# STM32.net
KiCad netlist of a schematic drawn in Altium Designer
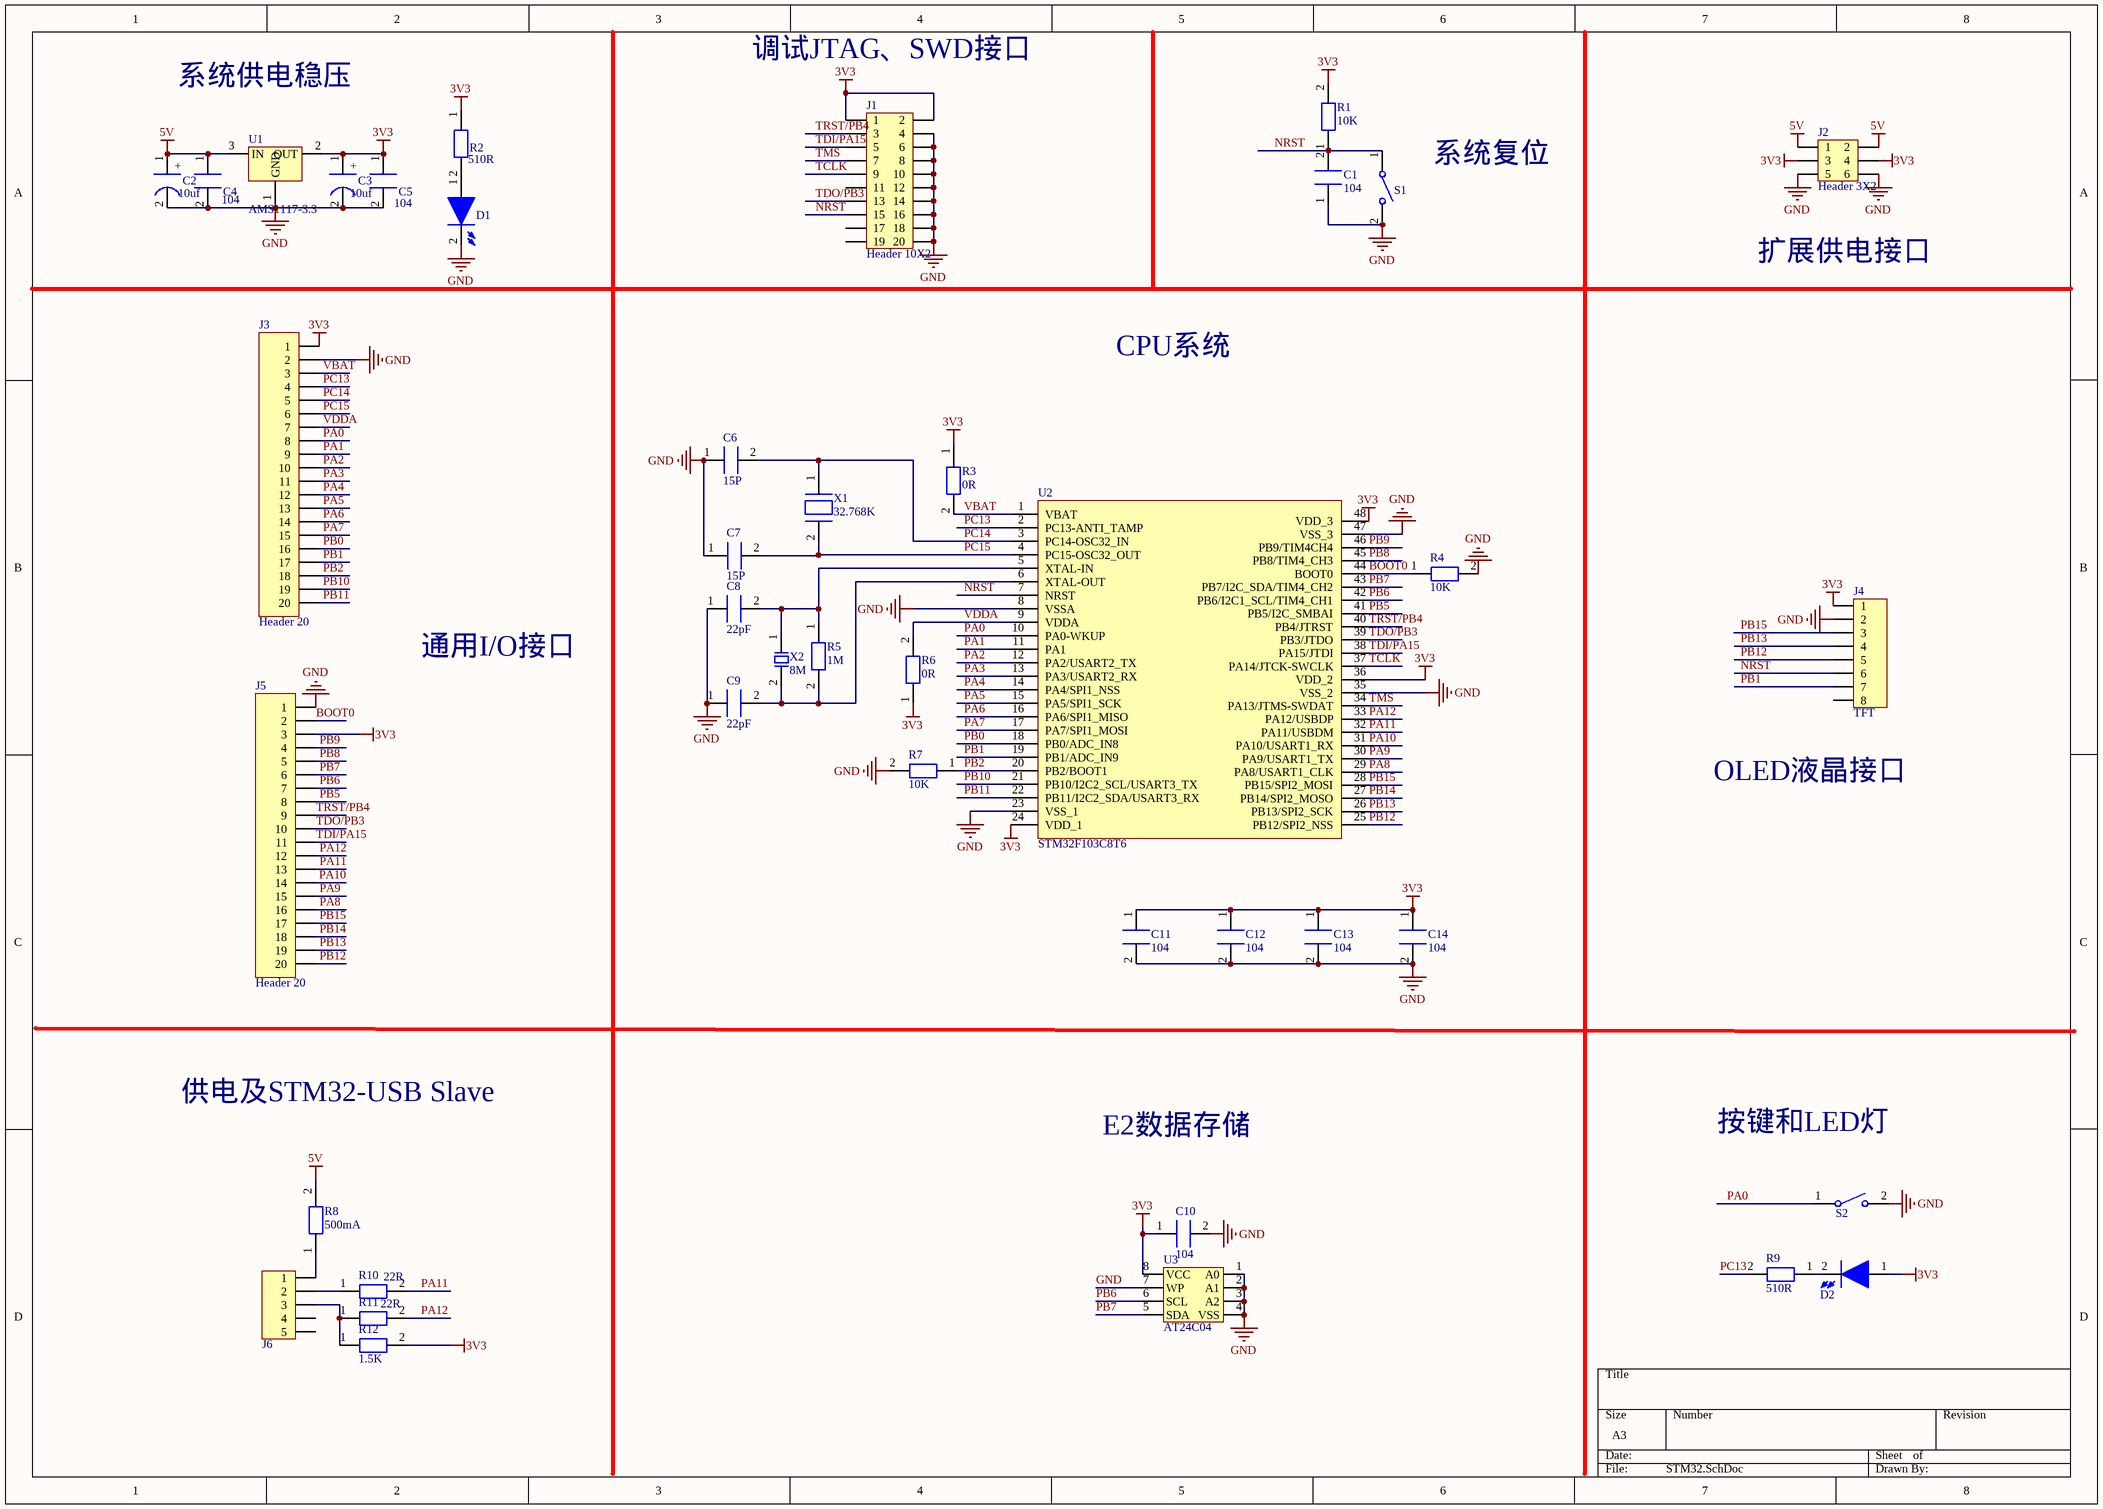
[diagram p0: STM32.SchDoc]

(export (version "E")
  (design (tool "Eeschema 10.0.6"))
  (components
    (comp (ref "C1")
      (value "104")
      (footprint "RC0603")
      (description "电容")
      (libsource (lib "STM32") (part "CAP"))
    )
    (comp (ref "C2")
      (value "10uf")
      (footprint "0805")
      (description "极性电容")
      (libsource (lib "STM32") (part "CAP+"))
    )
    (comp (ref "C3")
      (value "10uf")
      (footprint "0805")
      (description "极性电容")
      (libsource (lib "STM32") (part "CAP+"))
    )
    (comp (ref "C4")
      (value "104")
      (footprint "RC0603")
      (description "电容")
      (libsource (lib "STM32") (part "CAP"))
    )
    (comp (ref "C5")
      (value "104")
      (footprint "RC0603")
      (description "电容")
      (libsource (lib "STM32") (part "CAP"))
    )
    (comp (ref "C6")
      (value "15P")
      (footprint "RC0603")
      (description "电容")
      (libsource (lib "STM32") (part "CAP"))
    )
    (comp (ref "C7")
      (value "15P")
      (footprint "RC0603")
      (description "电容")
      (libsource (lib "STM32") (part "CAP"))
    )
    (comp (ref "C8")
      (value "22pF")
      (footprint "RC0603")
      (description "电容")
      (libsource (lib "STM32") (part "CAP"))
    )
    (comp (ref "C9")
      (value "22pF")
      (footprint "RC0603")
      (description "电容")
      (libsource (lib "STM32") (part "CAP"))
    )
    (comp (ref "C10")
      (value "104")
      (footprint "RC0603")
      (description "电容")
      (libsource (lib "STM32") (part "CAP"))
    )
    (comp (ref "C11")
      (value "104")
      (footprint "RC0603")
      (description "电容")
      (libsource (lib "STM32") (part "CAP"))
    )
    (comp (ref "C12")
      (value "104")
      (footprint "RC0603")
      (description "电容")
      (libsource (lib "STM32") (part "CAP"))
    )
    (comp (ref "C13")
      (value "104")
      (footprint "RC0603")
      (description "电容")
      (libsource (lib "STM32") (part "CAP"))
    )
    (comp (ref "C14")
      (value "104")
      (footprint "RC0603")
      (description "电容")
      (libsource (lib "STM32") (part "CAP"))
    )
    (comp (ref "D1")
      (value "LED0")
      (footprint "LED0805")
      (description "LED")
      (libsource (lib "STM32") (part "LED0"))
    )
    (comp (ref "D2")
      (value "LED0")
      (footprint "LED0805")
      (description "LED")
      (libsource (lib "STM32") (part "LED0"))
    )
    (comp (ref "J1")
      (value "Header 10X2")
      (footprint "JTAG_20P")
      (libsource (lib "STM32") (part "Header 10X2"))
    )
    (comp (ref "J2") (value "Header 3X2") (footprint "H-3X2") (libsource (lib "STM32") (part "Header 3X2")))
    (comp (ref "J3") (value "Header 20") (footprint "H 20") (libsource (lib "STM32") (part "Header 20")))
    (comp (ref "J4") (value "TFT") (footprint "H-8") (libsource (lib "STM32") (part "TFT")))
    (comp (ref "J5") (value "Header 20") (footprint "H 20") (libsource (lib "STM32") (part "Header 20")))
    (comp (ref "J6") (value "Mini-USB") (footprint "mini_USB") (libsource (lib "STM32") (part "Mini-USB")))
    (comp (ref "R1")
      (value "10K")
      (footprint "RC0603")
      (description "电阻")
      (libsource (lib "STM32") (part "RES"))
    )
    (comp (ref "R2")
      (value "510R")
      (footprint "RC0603")
      (description "电阻")
      (libsource (lib "STM32") (part "RES"))
    )
    (comp (ref "R3")
      (value "0R")
      (footprint "RC0603")
      (description "电阻")
      (libsource (lib "STM32") (part "RES"))
    )
    (comp (ref "R4")
      (value "10K")
      (footprint "RC0603")
      (description "电阻")
      (libsource (lib "STM32") (part "RES"))
    )
    (comp (ref "R5")
      (value "1M")
      (footprint "RC0603")
      (description "电阻")
      (libsource (lib "STM32") (part "RES"))
    )
    (comp (ref "R6")
      (value "0R")
      (footprint "RC0603")
      (description "电阻")
      (libsource (lib "STM32") (part "RES"))
    )
    (comp (ref "R7")
      (value "10K")
      (footprint "RC0603")
      (description "电阻")
      (libsource (lib "STM32") (part "RES"))
    )
    (comp (ref "R8")
      (value "500mA")
      (footprint "0805")
      (description "电阻")
      (libsource (lib "STM32") (part "RES"))
    )
    (comp (ref "R9")
      (value "510R")
      (footprint "RC0603")
      (description "电阻")
      (libsource (lib "STM32") (part "RES"))
    )
    (comp (ref "R10")
      (value "22R")
      (footprint "RC0603")
      (description "电阻")
      (libsource (lib "STM32") (part "RES"))
    )
    (comp (ref "R11")
      (value "22R")
      (footprint "RC0603")
      (description "电阻")
      (libsource (lib "STM32") (part "RES"))
    )
    (comp (ref "R12")
      (value "1.5K")
      (footprint "RC0603")
      (description "电阻")
      (libsource (lib "STM32") (part "RES"))
    )
    (comp (ref "S1")
      (value "SW-SPST")
      (footprint "SMT-KEY")
      (description "开关")
      (libsource (lib "STM32") (part "SW-SPST"))
    )
    (comp (ref "S2")
      (value "SW-SPST")
      (footprint "SMT-KEY")
      (description "开关")
      (libsource (lib "STM32") (part "SW-SPST"))
    )
    (comp (ref "U1")
      (value "AMS1117-3.3")
      (footprint "SOT223")
      (description "IC")
      (libsource (lib "STM32") (part "AMS1117-3.3"))
    )
    (comp (ref "U2")
      (value "STM32F103C8T6")
      (footprint "LQFP48")
      (description "IC")
      (libsource (lib "STM32") (part "STM32F103C8T6"))
    )
    (comp (ref "U3")
      (value "AT24C04")
      (footprint "SOIC-8")
      (description "IC")
      (libsource (lib "STM32") (part "AT24C04"))
    )
    (comp (ref "X1") (value "32.768K") (footprint "JZ32768") (libsource (lib "STM32") (part "32.768K")))
    (comp (ref "X2") (value "8M") (footprint "JZ49S") (libsource (lib "STM32") (part "8M")))
  )
  (nets
    (net (code "1") (name "/BOOT0") (class "Default")
      (node (ref "J5") (pin "2") (pinfunction "2_2") (pintype "passive"))
      (node (ref "R4") (pin "1") (pinfunction "1_1") (pintype "passive"))
      (node (ref "U2") (pin "44") (pinfunction "BOOT0_44") (pintype "passive"))
    )
    (net (code "2") (name "/NRST") (class "Default")
      (node (ref "C1") (pin "2") (pinfunction "2_2") (pintype "passive"))
      (node (ref "J1") (pin "15") (pinfunction "15_15") (pintype "passive"))
      (node (ref "J4") (pin "6") (pinfunction "6_6") (pintype "passive"))
      (node (ref "R1") (pin "1") (pinfunction "1_1") (pintype "passive"))
      (node (ref "S1") (pin "1") (pinfunction "1_1") (pintype "passive"))
      (node (ref "U2") (pin "7") (pinfunction "NRST_7") (pintype "passive"))
    )
    (net (code "3") (name "/PA0") (class "Default")
      (node (ref "J3") (pin "8") (pinfunction "8_8") (pintype "passive"))
      (node (ref "S2") (pin "1") (pinfunction "1_1") (pintype "passive"))
      (node (ref "U2") (pin "10") (pinfunction "PA0-WKUP_10") (pintype "passive"))
    )
    (net (code "4") (name "/PA1") (class "Default")
      (node (ref "J3") (pin "9") (pinfunction "9_9") (pintype "passive"))
      (node (ref "U2") (pin "11") (pinfunction "PA1_11") (pintype "passive"))
    )
    (net (code "5") (name "/PA2") (class "Default")
      (node (ref "J3") (pin "10") (pinfunction "10_10") (pintype "passive"))
      (node (ref "U2") (pin "12") (pinfunction "PA2/USART2_TX_12") (pintype "passive"))
    )
    (net (code "6") (name "/PA3") (class "Default")
      (node (ref "J3") (pin "11") (pinfunction "11_11") (pintype "passive"))
      (node (ref "U2") (pin "13") (pinfunction "PA3/USART2_RX_13") (pintype "passive"))
    )
    (net (code "7") (name "/PA4") (class "Default")
      (node (ref "J3") (pin "12") (pinfunction "12_12") (pintype "passive"))
      (node (ref "U2") (pin "14") (pinfunction "PA4/SPI1_NSS_14") (pintype "passive"))
    )
    (net (code "8") (name "/PA5") (class "Default")
      (node (ref "J3") (pin "13") (pinfunction "13_13") (pintype "passive"))
      (node (ref "U2") (pin "15") (pinfunction "PA5/SPI1_SCK_15") (pintype "passive"))
    )
    (net (code "9") (name "/PA6") (class "Default")
      (node (ref "J3") (pin "14") (pinfunction "14_14") (pintype "passive"))
      (node (ref "U2") (pin "16") (pinfunction "PA6/SPI1_MISO_16") (pintype "passive"))
    )
    (net (code "10") (name "/PA7") (class "Default")
      (node (ref "J3") (pin "15") (pinfunction "15_15") (pintype "passive"))
      (node (ref "U2") (pin "17") (pinfunction "PA7/SPI1_MOSI_17") (pintype "passive"))
    )
    (net (code "11") (name "/PA8") (class "Default")
      (node (ref "J5") (pin "16") (pinfunction "16_16") (pintype "passive"))
      (node (ref "U2") (pin "29") (pinfunction "PA8/USART1_CLK_29") (pintype "passive"))
    )
    (net (code "12") (name "/PA9") (class "Default")
      (node (ref "J5") (pin "15") (pinfunction "15_15") (pintype "passive"))
      (node (ref "U2") (pin "30") (pinfunction "PA9/USART1_TX_30") (pintype "passive"))
    )
    (net (code "13") (name "/PA10") (class "Default")
      (node (ref "J5") (pin "14") (pinfunction "14_14") (pintype "passive"))
      (node (ref "U2") (pin "31") (pinfunction "PA10/USART1_RX_31") (pintype "passive"))
    )
    (net (code "14") (name "/PA11") (class "Default")
      (node (ref "J5") (pin "13") (pinfunction "13_13") (pintype "passive"))
      (node (ref "R10") (pin "2") (pinfunction "2_2") (pintype "passive"))
      (node (ref "U2") (pin "32") (pinfunction "PA11/USBDM_32") (pintype "passive"))
    )
    (net (code "15") (name "/PA12") (class "Default")
      (node (ref "J5") (pin "12") (pinfunction "12_12") (pintype "passive"))
      (node (ref "R11") (pin "2") (pinfunction "2_2") (pintype "passive"))
      (node (ref "U2") (pin "33") (pinfunction "PA12/USBDP_33") (pintype "passive"))
    )
    (net (code "16") (name "/PB0") (class "Default")
      (node (ref "J3") (pin "16") (pinfunction "16_16") (pintype "passive"))
      (node (ref "U2") (pin "18") (pinfunction "PB0/ADC_IN8_18") (pintype "passive"))
    )
    (net (code "17") (name "/PB1") (class "Default")
      (node (ref "J3") (pin "17") (pinfunction "17_17") (pintype "passive"))
      (node (ref "J4") (pin "7") (pinfunction "7_7") (pintype "passive"))
      (node (ref "U2") (pin "19") (pinfunction "PB1/ADC_IN9_19") (pintype "passive"))
    )
    (net (code "18") (name "/PB2") (class "Default")
      (node (ref "J3") (pin "18") (pinfunction "18_18") (pintype "passive"))
      (node (ref "R7") (pin "1") (pinfunction "1_1") (pintype "passive"))
      (node (ref "U2") (pin "20") (pinfunction "PB2/BOOT1_20") (pintype "passive"))
    )
    (net (code "19") (name "/PB5") (class "Default")
      (node (ref "J5") (pin "8") (pinfunction "8_8") (pintype "passive"))
      (node (ref "U2") (pin "41") (pinfunction "PB5/I2C_SMBAI_41") (pintype "passive"))
    )
    (net (code "20") (name "/PB6") (class "Default")
      (node (ref "J5") (pin "7") (pinfunction "7_7") (pintype "passive"))
      (node (ref "U2") (pin "42") (pinfunction "PB6/I2C1_SCL/TIM4_CH1_42") (pintype "passive"))
      (node (ref "U3") (pin "6") (pinfunction "SCL_6") (pintype "passive"))
    )
    (net (code "21") (name "/PB7") (class "Default")
      (node (ref "J5") (pin "6") (pinfunction "6_6") (pintype "passive"))
      (node (ref "U2") (pin "43") (pinfunction "PB7/I2C_SDA/TIM4_CH2_43") (pintype "passive"))
      (node (ref "U3") (pin "5") (pinfunction "SDA_5") (pintype "passive"))
    )
    (net (code "22") (name "/PB8") (class "Default")
      (node (ref "J5") (pin "5") (pinfunction "5_5") (pintype "passive"))
      (node (ref "U2") (pin "45") (pinfunction "PB8/TIM4_CH3_45") (pintype "passive"))
    )
    (net (code "23") (name "/PB9") (class "Default")
      (node (ref "J5") (pin "4") (pinfunction "4_4") (pintype "passive"))
      (node (ref "U2") (pin "46") (pinfunction "PB9/TIM4CH4_46") (pintype "passive"))
    )
    (net (code "24") (name "/PB10") (class "Default")
      (node (ref "J3") (pin "19") (pinfunction "19_19") (pintype "passive"))
      (node (ref "U2") (pin "21") (pinfunction "PB10/I2C2_SCL/USART3_TX_21") (pintype "passive"))
    )
    (net (code "25") (name "/PB11") (class "Default")
      (node (ref "J3") (pin "20") (pinfunction "20_20") (pintype "passive"))
      (node (ref "U2") (pin "22") (pinfunction "PB11/I2C2_SDA/USART3_RX_22") (pintype "passive"))
    )
    (net (code "26") (name "/PB12") (class "Default")
      (node (ref "J4") (pin "5") (pinfunction "5_5") (pintype "passive"))
      (node (ref "J5") (pin "20") (pinfunction "20_20") (pintype "passive"))
      (node (ref "U2") (pin "25") (pinfunction "PB12/SPI2_NSS_25") (pintype "passive"))
    )
    (net (code "27") (name "/PB13") (class "Default")
      (node (ref "J4") (pin "4") (pinfunction "4_4") (pintype "passive"))
      (node (ref "J5") (pin "19") (pinfunction "19_19") (pintype "passive"))
      (node (ref "U2") (pin "26") (pinfunction "PB13/SPI2_SCK_26") (pintype "passive"))
    )
    (net (code "28") (name "/PB14") (class "Default")
      (node (ref "J5") (pin "18") (pinfunction "18_18") (pintype "passive"))
      (node (ref "U2") (pin "27") (pinfunction "PB14/SPI2_MOSO_27") (pintype "passive"))
    )
    (net (code "29") (name "/PB15") (class "Default")
      (node (ref "J4") (pin "3") (pinfunction "3_3") (pintype "passive"))
      (node (ref "J5") (pin "17") (pinfunction "17_17") (pintype "passive"))
      (node (ref "U2") (pin "28") (pinfunction "PB15/SPI2_MOSI_28") (pintype "passive"))
    )
    (net (code "30") (name "/PC13") (class "Default")
      (node (ref "J3") (pin "4") (pinfunction "4_4") (pintype "passive"))
      (node (ref "R9") (pin "2") (pinfunction "2_2") (pintype "passive"))
      (node (ref "U2") (pin "2") (pinfunction "PC13-ANTI_TAMP_2") (pintype "passive"))
    )
    (net (code "31") (name "/PC14") (class "Default")
      (node (ref "C6") (pin "2") (pinfunction "2_2") (pintype "passive"))
      (node (ref "J3") (pin "5") (pinfunction "5_5") (pintype "passive"))
      (node (ref "U2") (pin "3") (pinfunction "PC14-OSC32_IN_3") (pintype "passive"))
      (node (ref "X1") (pin "1") (pinfunction "1_1") (pintype "passive"))
    )
    (net (code "32") (name "/PC15") (class "Default")
      (node (ref "C7") (pin "2") (pinfunction "2_2") (pintype "passive"))
      (node (ref "J3") (pin "6") (pinfunction "6_6") (pintype "passive"))
      (node (ref "U2") (pin "4") (pinfunction "PC15-OSC32_OUT_4") (pintype "passive"))
      (node (ref "X1") (pin "2") (pinfunction "2_2") (pintype "passive"))
    )
    (net (code "33") (name "/TCLK") (class "Default")
      (node (ref "J1") (pin "9") (pinfunction "9_9") (pintype "passive"))
      (node (ref "U2") (pin "37") (pinfunction "PA14/JTCK-SWCLK_37") (pintype "passive"))
    )
    (net (code "34") (name "/TDI{slash}PA15") (class "Default")
      (node (ref "J1") (pin "5") (pinfunction "5_5") (pintype "passive"))
      (node (ref "J5") (pin "11") (pinfunction "11_11") (pintype "passive"))
      (node (ref "U2") (pin "38") (pinfunction "PA15/JTDI_38") (pintype "passive"))
    )
    (net (code "35") (name "/TDO{slash}PB3") (class "Default")
      (node (ref "J1") (pin "13") (pinfunction "13_13") (pintype "passive"))
      (node (ref "J5") (pin "10") (pinfunction "10_10") (pintype "passive"))
      (node (ref "U2") (pin "39") (pinfunction "PB3/JTDO_39") (pintype "passive"))
    )
    (net (code "36") (name "/TMS") (class "Default")
      (node (ref "J1") (pin "7") (pinfunction "7_7") (pintype "passive"))
      (node (ref "U2") (pin "34") (pinfunction "PA13/JTMS-SWDAT_34") (pintype "passive"))
    )
    (net (code "37") (name "/TRST{slash}PB4") (class "Default")
      (node (ref "J1") (pin "3") (pinfunction "3_3") (pintype "passive"))
      (node (ref "J5") (pin "9") (pinfunction "9_9") (pintype "passive"))
      (node (ref "U2") (pin "40") (pinfunction "PB4/JTRST_40") (pintype "passive"))
    )
    (net (code "38") (name "/VBAT") (class "Default")
      (node (ref "J3") (pin "3") (pinfunction "3_3") (pintype "passive"))
      (node (ref "R3") (pin "2") (pinfunction "2_2") (pintype "passive"))
      (node (ref "U2") (pin "1") (pinfunction "VBAT_1") (pintype "passive"))
    )
    (net (code "39") (name "/VDDA") (class "Default")
      (node (ref "J3") (pin "7") (pinfunction "7_7") (pintype "passive"))
      (node (ref "R6") (pin "2") (pinfunction "2_2") (pintype "passive"))
      (node (ref "U2") (pin "9") (pinfunction "VDDA_9") (pintype "passive"))
    )
    (net (code "40") (name "3V3") (class "Default")
      (node (ref "C10") (pin "1") (pinfunction "1_1") (pintype "passive"))
      (node (ref "C11") (pin "1") (pinfunction "1_1") (pintype "passive"))
      (node (ref "C12") (pin "1") (pinfunction "1_1") (pintype "passive"))
      (node (ref "C13") (pin "1") (pinfunction "1_1") (pintype "passive"))
      (node (ref "C14") (pin "1") (pinfunction "1_1") (pintype "passive"))
      (node (ref "C3") (pin "1") (pinfunction "1_1") (pintype "passive"))
      (node (ref "C5") (pin "1") (pinfunction "1_1") (pintype "passive"))
      (node (ref "D2") (pin "1") (pinfunction "1_1") (pintype "passive"))
      (node (ref "J1") (pin "1") (pinfunction "1_1") (pintype "passive"))
      (node (ref "J1") (pin "2") (pinfunction "2_2") (pintype "passive"))
      (node (ref "J2") (pin "3") (pinfunction "3_3") (pintype "passive"))
      (node (ref "J2") (pin "4") (pinfunction "4_4") (pintype "passive"))
      (node (ref "J3") (pin "1") (pinfunction "1_1") (pintype "passive"))
      (node (ref "J4") (pin "1") (pinfunction "1_1") (pintype "passive"))
      (node (ref "J5") (pin "3") (pinfunction "3_3") (pintype "passive"))
      (node (ref "R1") (pin "2") (pinfunction "2_2") (pintype "passive"))
      (node (ref "R12") (pin "2") (pinfunction "2_2") (pintype "passive"))
      (node (ref "R2") (pin "1") (pinfunction "1_1") (pintype "passive"))
      (node (ref "R3") (pin "1") (pinfunction "1_1") (pintype "passive"))
      (node (ref "R6") (pin "1") (pinfunction "1_1") (pintype "passive"))
      (node (ref "U1") (pin "2") (pinfunction "OUT_2") (pintype "passive"))
      (node (ref "U2") (pin "24") (pinfunction "VDD_1_24") (pintype "passive"))
      (node (ref "U2") (pin "36") (pinfunction "VDD_2_36") (pintype "passive"))
      (node (ref "U2") (pin "48") (pinfunction "VDD_3_48") (pintype "passive"))
      (node (ref "U3") (pin "8") (pinfunction "VCC_8") (pintype "passive"))
    )
    (net (code "41") (name "5V") (class "Default")
      (node (ref "C2") (pin "1") (pinfunction "1_1") (pintype "passive"))
      (node (ref "C4") (pin "1") (pinfunction "1_1") (pintype "passive"))
      (node (ref "J2") (pin "1") (pinfunction "1_1") (pintype "passive"))
      (node (ref "J2") (pin "2") (pinfunction "2_2") (pintype "passive"))
      (node (ref "R8") (pin "2") (pinfunction "2_2") (pintype "passive"))
      (node (ref "U1") (pin "3") (pinfunction "IN_3") (pintype "passive"))
    )
    (net (code "42") (name "GND") (class "Default")
      (node (ref "C1") (pin "1") (pinfunction "1_1") (pintype "passive"))
      (node (ref "C10") (pin "2") (pinfunction "2_2") (pintype "passive"))
      (node (ref "C11") (pin "2") (pinfunction "2_2") (pintype "passive"))
      (node (ref "C12") (pin "2") (pinfunction "2_2") (pintype "passive"))
      (node (ref "C13") (pin "2") (pinfunction "2_2") (pintype "passive"))
      (node (ref "C14") (pin "2") (pinfunction "2_2") (pintype "passive"))
      (node (ref "C2") (pin "2") (pinfunction "2_2") (pintype "passive"))
      (node (ref "C3") (pin "2") (pinfunction "2_2") (pintype "passive"))
      (node (ref "C4") (pin "2") (pinfunction "2_2") (pintype "passive"))
      (node (ref "C5") (pin "2") (pinfunction "2_2") (pintype "passive"))
      (node (ref "C6") (pin "1") (pinfunction "1_1") (pintype "passive"))
      (node (ref "C7") (pin "1") (pinfunction "1_1") (pintype "passive"))
      (node (ref "C8") (pin "1") (pinfunction "1_1") (pintype "passive"))
      (node (ref "C9") (pin "1") (pinfunction "1_1") (pintype "passive"))
      (node (ref "D1") (pin "2") (pinfunction "2_2") (pintype "passive"))
      (node (ref "J1") (pin "10") (pinfunction "10_10") (pintype "passive"))
      (node (ref "J1") (pin "12") (pinfunction "12_12") (pintype "passive"))
      (node (ref "J1") (pin "14") (pinfunction "14_14") (pintype "passive"))
      (node (ref "J1") (pin "16") (pinfunction "16_16") (pintype "passive"))
      (node (ref "J1") (pin "18") (pinfunction "18_18") (pintype "passive"))
      (node (ref "J1") (pin "20") (pinfunction "20_20") (pintype "passive"))
      (node (ref "J1") (pin "4") (pinfunction "4_4") (pintype "passive"))
      (node (ref "J1") (pin "6") (pinfunction "6_6") (pintype "passive"))
      (node (ref "J1") (pin "8") (pinfunction "8_8") (pintype "passive"))
      (node (ref "J2") (pin "5") (pinfunction "5_5") (pintype "passive"))
      (node (ref "J2") (pin "6") (pinfunction "6_6") (pintype "passive"))
      (node (ref "J3") (pin "2") (pinfunction "2_2") (pintype "passive"))
      (node (ref "J4") (pin "2") (pinfunction "2_2") (pintype "passive"))
      (node (ref "J5") (pin "1") (pinfunction "1_1") (pintype "passive"))
      (node (ref "R4") (pin "2") (pinfunction "2_2") (pintype "passive"))
      (node (ref "R7") (pin "2") (pinfunction "2_2") (pintype "passive"))
      (node (ref "S1") (pin "2") (pinfunction "2_2") (pintype "passive"))
      (node (ref "S2") (pin "2") (pinfunction "2_2") (pintype "passive"))
      (node (ref "U1") (pin "1") (pinfunction "GND_1") (pintype "passive"))
      (node (ref "U2") (pin "23") (pinfunction "VSS_1_23") (pintype "passive"))
      (node (ref "U2") (pin "35") (pinfunction "VSS_2_35") (pintype "passive"))
      (node (ref "U2") (pin "47") (pinfunction "VSS_3_47") (pintype "passive"))
      (node (ref "U2") (pin "8") (pinfunction "VSSA_8") (pintype "passive"))
      (node (ref "U3") (pin "1") (pinfunction "A0_1") (pintype "passive"))
      (node (ref "U3") (pin "2") (pinfunction "A1_2") (pintype "passive"))
      (node (ref "U3") (pin "3") (pinfunction "A2_3") (pintype "passive"))
      (node (ref "U3") (pin "4") (pinfunction "VSS_4") (pintype "passive"))
      (node (ref "U3") (pin "7") (pinfunction "WP_7") (pintype "passive"))
    )
    (net (code "43") (name "Net-(D1-Pad1)") (class "Default")
      (node (ref "D1") (pin "1") (pinfunction "1_1") (pintype "passive"))
      (node (ref "R2") (pin "2") (pinfunction "2_2") (pintype "passive"))
    )
    (net (code "44") (name "Net-(D2-Pad2)") (class "Default")
      (node (ref "D2") (pin "2") (pinfunction "2_2") (pintype "passive"))
      (node (ref "R9") (pin "1") (pinfunction "1_1") (pintype "passive"))
    )
    (net (code "45") (name "Net-(J6-Pad1)") (class "Default")
      (node (ref "J6") (pin "1") (pinfunction "1_1") (pintype "passive"))
      (node (ref "R8") (pin "1") (pinfunction "1_1") (pintype "passive"))
    )
    (net (code "46") (name "Net-(J6-Pad2)") (class "Default")
      (node (ref "J6") (pin "2") (pinfunction "2_2") (pintype "passive"))
      (node (ref "R10") (pin "1") (pinfunction "1_1") (pintype "passive"))
    )
    (net (code "47") (name "Net-(J6-Pad3)") (class "Default")
      (node (ref "J6") (pin "3") (pinfunction "3_3") (pintype "passive"))
      (node (ref "R11") (pin "1") (pinfunction "1_1") (pintype "passive"))
      (node (ref "R12") (pin "1") (pinfunction "1_1") (pintype "passive"))
    )
    (net (code "48") (name "Net-(U2-XTAL-IN)") (class "Default")
      (node (ref "C8") (pin "2") (pinfunction "2_2") (pintype "passive"))
      (node (ref "R5") (pin "1") (pinfunction "1_1") (pintype "passive"))
      (node (ref "U2") (pin "5") (pinfunction "XTAL-IN_5") (pintype "passive"))
      (node (ref "X2") (pin "1") (pinfunction "1_1") (pintype "passive"))
    )
    (net (code "49") (name "Net-(U2-XTAL-OUT)") (class "Default")
      (node (ref "C9") (pin "2") (pinfunction "2_2") (pintype "passive"))
      (node (ref "R5") (pin "2") (pinfunction "2_2") (pintype "passive"))
      (node (ref "U2") (pin "6") (pinfunction "XTAL-OUT_6") (pintype "passive"))
      (node (ref "X2") (pin "2") (pinfunction "2_2") (pintype "passive"))
    )
    (net (code "50") (name "unconnected-(J1-Pad11)") (class "Default")
      (node (ref "J1") (pin "11") (pinfunction "11_11") (pintype "passive"))
    )
    (net (code "51") (name "unconnected-(J1-Pad17)") (class "Default")
      (node (ref "J1") (pin "17") (pinfunction "17_17") (pintype "passive"))
    )
    (net (code "52") (name "unconnected-(J1-Pad19)") (class "Default")
      (node (ref "J1") (pin "19") (pinfunction "19_19") (pintype "passive"))
    )
    (net (code "53") (name "unconnected-(J4-Pad8)") (class "Default")
      (node (ref "J4") (pin "8") (pinfunction "8_8") (pintype "passive"))
    )
    (net (code "54") (name "unconnected-(J6-Pad4)") (class "Default")
      (node (ref "J6") (pin "4") (pinfunction "4_4") (pintype "passive"))
    )
    (net (code "55") (name "unconnected-(J6-Pad5)") (class "Default")
      (node (ref "J6") (pin "5") (pinfunction "5_5") (pintype "passive"))
    )
  )
)
